# M624A.net
KiCad netlist of a schematic drawn in EAGLE
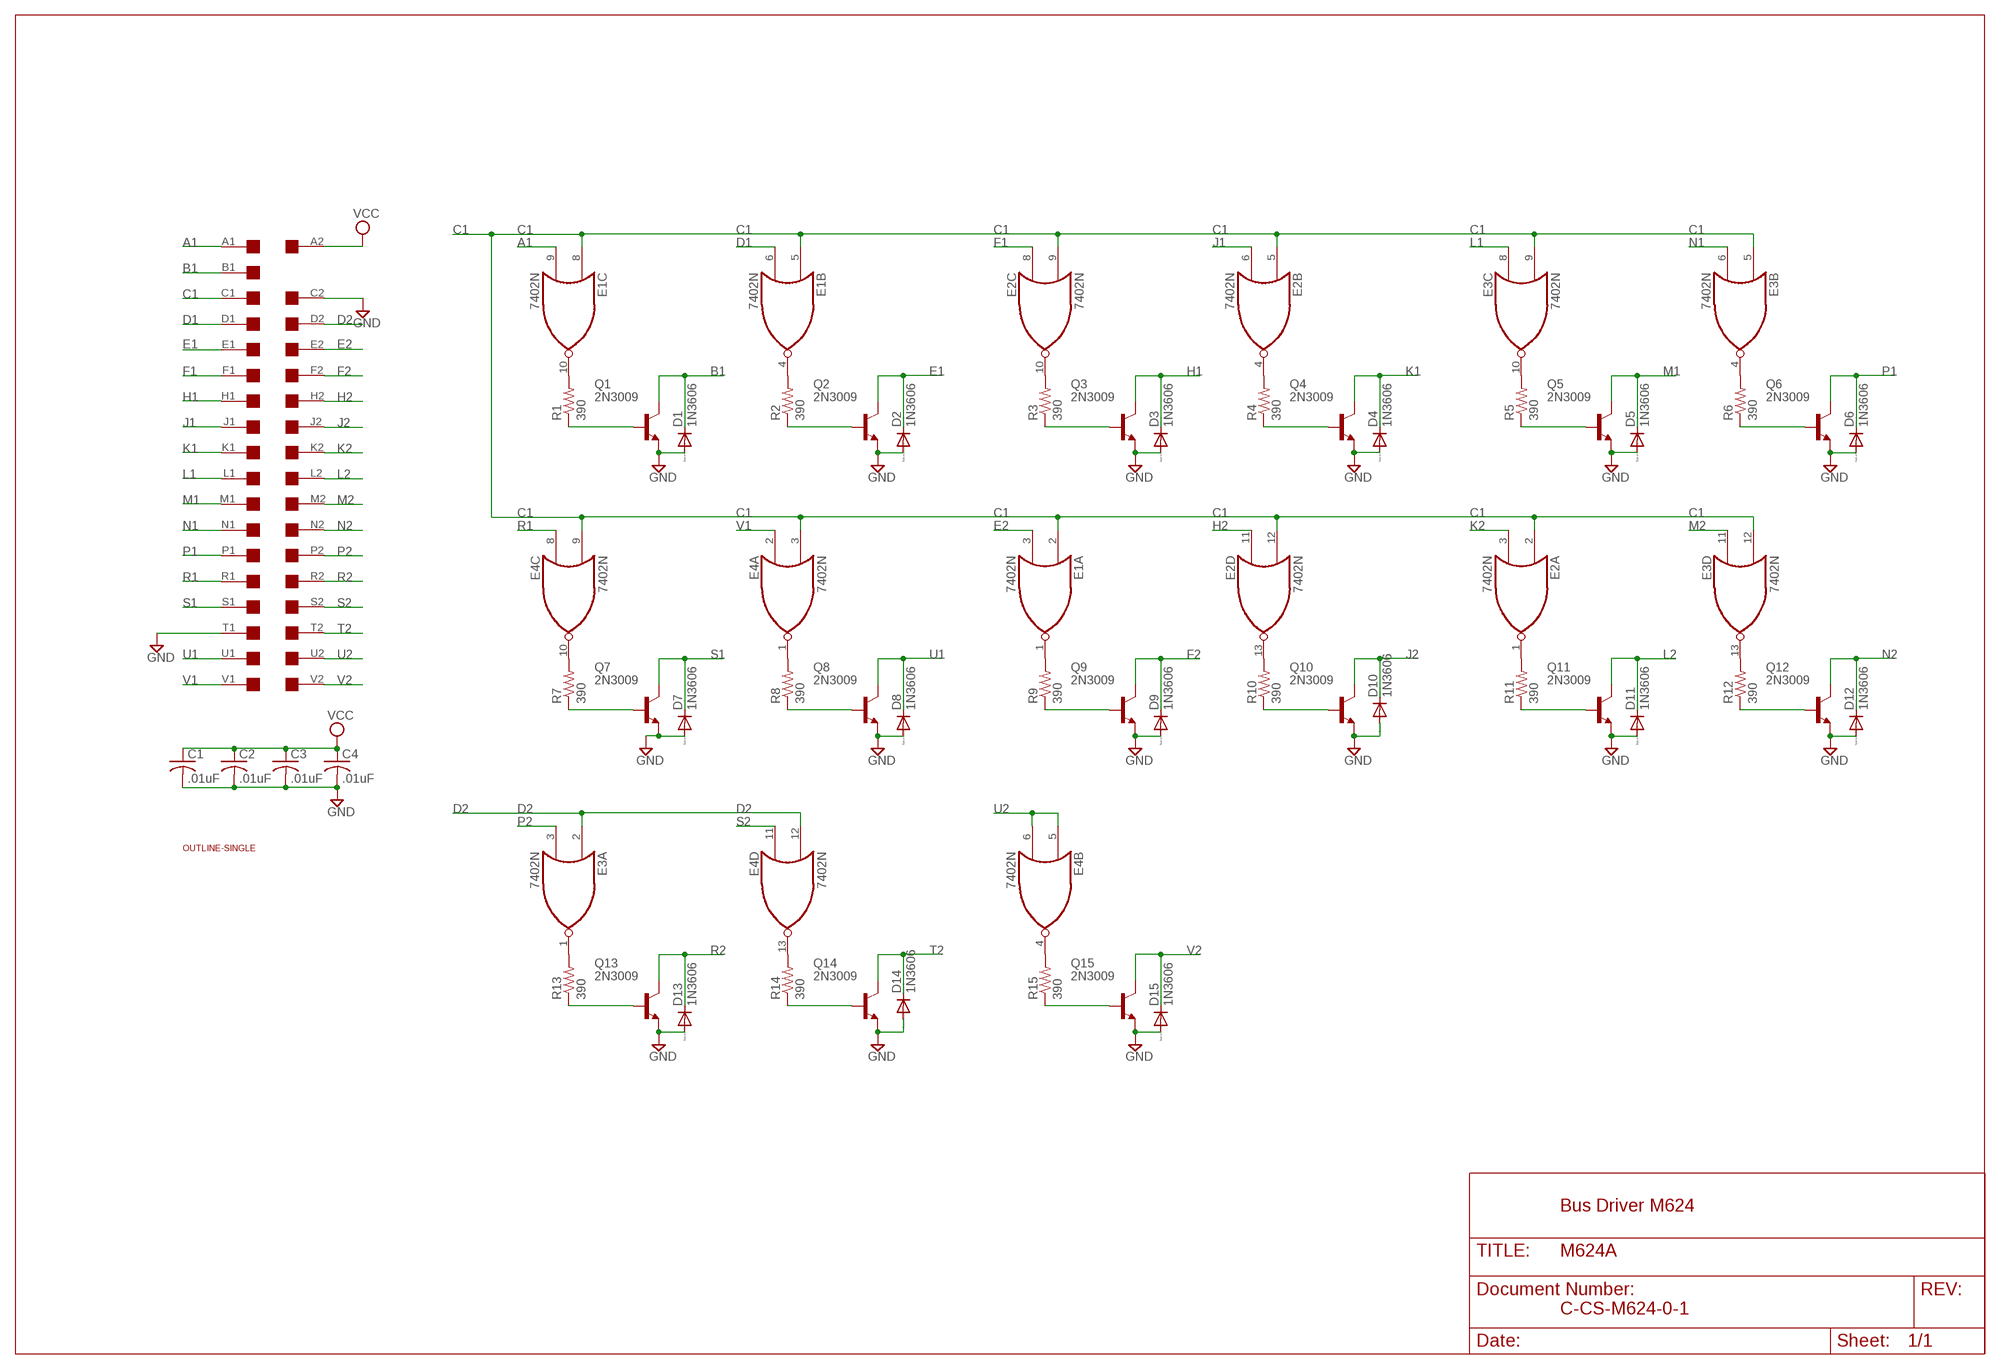
[diagram p0: schematic, sheet 1]

(export (version "E")
  (design (tool "Eeschema 10.0.6"))
  (components
    (comp (ref "C1")
      (value ".01uF")
      (footprint "eagle-import:C050-025X075")
      (libsource (lib "eagle-import") (part "C-US050-025X075"))
    )
    (comp (ref "C2")
      (value ".01uF")
      (footprint "eagle-import:C050-025X075")
      (libsource (lib "eagle-import") (part "C-US050-025X075"))
    )
    (comp (ref "C3")
      (value ".01uF")
      (footprint "eagle-import:C050-025X075")
      (libsource (lib "eagle-import") (part "C-US050-025X075"))
    )
    (comp (ref "C4")
      (value ".01uF")
      (footprint "eagle-import:C050-025X075")
      (libsource (lib "eagle-import") (part "C-US050-025X075"))
    )
    (comp (ref "D1")
      (value "1N3606")
      (footprint "eagle-import:DO35-10")
      (libsource (lib "eagle-import") (part "1N4148DO35-10"))
    )
    (comp (ref "D2")
      (value "1N3606")
      (footprint "eagle-import:DO35-10")
      (libsource (lib "eagle-import") (part "1N4148DO35-10"))
    )
    (comp (ref "D3")
      (value "1N3606")
      (footprint "eagle-import:DO35-10")
      (libsource (lib "eagle-import") (part "1N4148DO35-10"))
    )
    (comp (ref "D4")
      (value "1N3606")
      (footprint "eagle-import:DO35-10")
      (libsource (lib "eagle-import") (part "1N4148DO35-10"))
    )
    (comp (ref "D5")
      (value "1N3606")
      (footprint "eagle-import:DO35-10")
      (libsource (lib "eagle-import") (part "1N4148DO35-10"))
    )
    (comp (ref "D6")
      (value "1N3606")
      (footprint "eagle-import:DO35-10")
      (libsource (lib "eagle-import") (part "1N4148DO35-10"))
    )
    (comp (ref "D7")
      (value "1N3606")
      (footprint "eagle-import:DO35-10")
      (libsource (lib "eagle-import") (part "1N4148DO35-10"))
    )
    (comp (ref "D8")
      (value "1N3606")
      (footprint "eagle-import:DO35-10")
      (libsource (lib "eagle-import") (part "1N4148DO35-10"))
    )
    (comp (ref "D9")
      (value "1N3606")
      (footprint "eagle-import:DO35-10")
      (libsource (lib "eagle-import") (part "1N4148DO35-10"))
    )
    (comp (ref "D10")
      (value "1N3606")
      (footprint "eagle-import:DO35-10")
      (libsource (lib "eagle-import") (part "1N4148DO35-10"))
    )
    (comp (ref "D11")
      (value "1N3606")
      (footprint "eagle-import:DO35-10")
      (libsource (lib "eagle-import") (part "1N4148DO35-10"))
    )
    (comp (ref "D12")
      (value "1N3606")
      (footprint "eagle-import:DO35-10")
      (libsource (lib "eagle-import") (part "1N4148DO35-10"))
    )
    (comp (ref "D13")
      (value "1N3606")
      (footprint "eagle-import:DO35-10")
      (libsource (lib "eagle-import") (part "1N4148DO35-10"))
    )
    (comp (ref "D14")
      (value "1N3606")
      (footprint "eagle-import:DO35-10")
      (libsource (lib "eagle-import") (part "1N4148DO35-10"))
    )
    (comp (ref "D15")
      (value "1N3606")
      (footprint "eagle-import:DO35-10")
      (libsource (lib "eagle-import") (part "1N4148DO35-10"))
    )
    (comp (ref "E1")
      (value "7402N")
      (footprint "eagle-import:DIL14")
      (libsource (lib "eagle-import") (part "7402N"))
    )
    (comp (ref "E2")
      (value "7402N")
      (footprint "eagle-import:DIL14")
      (libsource (lib "eagle-import") (part "7402N"))
    )
    (comp (ref "E3")
      (value "7402N")
      (footprint "eagle-import:DIL14")
      (libsource (lib "eagle-import") (part "7402N"))
    )
    (comp (ref "E4")
      (value "7402N")
      (footprint "eagle-import:DIL14")
      (libsource (lib "eagle-import") (part "7402N"))
    )
    (comp (ref "Q1")
      (value "2N3009")
      (footprint "eagle-import:TO39")
      (libsource (lib "eagle-import") (part "-NPN-TO39-EBC2N1613"))
    )
    (comp (ref "Q2")
      (value "2N3009")
      (footprint "eagle-import:TO39")
      (libsource (lib "eagle-import") (part "-NPN-TO39-EBC2N1613"))
    )
    (comp (ref "Q3")
      (value "2N3009")
      (footprint "eagle-import:TO39")
      (libsource (lib "eagle-import") (part "-NPN-TO39-EBC2N1613"))
    )
    (comp (ref "Q4")
      (value "2N3009")
      (footprint "eagle-import:TO39")
      (libsource (lib "eagle-import") (part "-NPN-TO39-EBC2N1613"))
    )
    (comp (ref "Q5")
      (value "2N3009")
      (footprint "eagle-import:TO39")
      (libsource (lib "eagle-import") (part "-NPN-TO39-EBC2N1613"))
    )
    (comp (ref "Q6")
      (value "2N3009")
      (footprint "eagle-import:TO39")
      (libsource (lib "eagle-import") (part "-NPN-TO39-EBC2N1613"))
    )
    (comp (ref "Q7")
      (value "2N3009")
      (footprint "eagle-import:TO39")
      (libsource (lib "eagle-import") (part "-NPN-TO39-EBC2N1613"))
    )
    (comp (ref "Q8")
      (value "2N3009")
      (footprint "eagle-import:TO39")
      (libsource (lib "eagle-import") (part "-NPN-TO39-EBC2N1613"))
    )
    (comp (ref "Q9")
      (value "2N3009")
      (footprint "eagle-import:TO39")
      (libsource (lib "eagle-import") (part "-NPN-TO39-EBC2N1613"))
    )
    (comp (ref "Q10")
      (value "2N3009")
      (footprint "eagle-import:TO39")
      (libsource (lib "eagle-import") (part "-NPN-TO39-EBC2N1613"))
    )
    (comp (ref "Q11")
      (value "2N3009")
      (footprint "eagle-import:TO39")
      (libsource (lib "eagle-import") (part "-NPN-TO39-EBC2N1613"))
    )
    (comp (ref "Q12")
      (value "2N3009")
      (footprint "eagle-import:TO39")
      (libsource (lib "eagle-import") (part "-NPN-TO39-EBC2N1613"))
    )
    (comp (ref "Q13")
      (value "2N3009")
      (footprint "eagle-import:TO39")
      (libsource (lib "eagle-import") (part "-NPN-TO39-EBC2N1613"))
    )
    (comp (ref "Q14")
      (value "2N3009")
      (footprint "eagle-import:TO39")
      (libsource (lib "eagle-import") (part "-NPN-TO39-EBC2N1613"))
    )
    (comp (ref "Q15")
      (value "2N3009")
      (footprint "eagle-import:TO39")
      (libsource (lib "eagle-import") (part "-NPN-TO39-EBC2N1613"))
    )
    (comp (ref "R1")
      (value "390")
      (footprint "eagle-import:0207_10")
      (libsource (lib "eagle-import") (part "R-US_0207/10"))
    )
    (comp (ref "R2")
      (value "390")
      (footprint "eagle-import:0207_10")
      (libsource (lib "eagle-import") (part "R-US_0207/10"))
    )
    (comp (ref "R3")
      (value "390")
      (footprint "eagle-import:0207_10")
      (libsource (lib "eagle-import") (part "R-US_0207/10"))
    )
    (comp (ref "R4")
      (value "390")
      (footprint "eagle-import:0207_10")
      (libsource (lib "eagle-import") (part "R-US_0207/10"))
    )
    (comp (ref "R5")
      (value "390")
      (footprint "eagle-import:0207_10")
      (libsource (lib "eagle-import") (part "R-US_0207/10"))
    )
    (comp (ref "R6")
      (value "390")
      (footprint "eagle-import:0207_10")
      (libsource (lib "eagle-import") (part "R-US_0207/10"))
    )
    (comp (ref "R7")
      (value "390")
      (footprint "eagle-import:0207_10")
      (libsource (lib "eagle-import") (part "R-US_0207/10"))
    )
    (comp (ref "R8")
      (value "390")
      (footprint "eagle-import:0207_10")
      (libsource (lib "eagle-import") (part "R-US_0207/10"))
    )
    (comp (ref "R9")
      (value "390")
      (footprint "eagle-import:0207_10")
      (libsource (lib "eagle-import") (part "R-US_0207/10"))
    )
    (comp (ref "R10")
      (value "390")
      (footprint "eagle-import:0207_10")
      (libsource (lib "eagle-import") (part "R-US_0207/10"))
    )
    (comp (ref "R11")
      (value "390")
      (footprint "eagle-import:0207_10")
      (libsource (lib "eagle-import") (part "R-US_0207/10"))
    )
    (comp (ref "R12")
      (value "390")
      (footprint "eagle-import:0207_10")
      (libsource (lib "eagle-import") (part "R-US_0207/10"))
    )
    (comp (ref "R13")
      (value "390")
      (footprint "eagle-import:0207_10")
      (libsource (lib "eagle-import") (part "R-US_0207/10"))
    )
    (comp (ref "R14")
      (value "390")
      (footprint "eagle-import:0207_10")
      (libsource (lib "eagle-import") (part "R-US_0207/10"))
    )
    (comp (ref "R15")
      (value "390")
      (footprint "eagle-import:0207_10")
      (libsource (lib "eagle-import") (part "R-US_0207/10"))
    )
    (comp (ref "U$1")
      (value "OUTLINE-SINGLE")
      (footprint "eagle-import:SINGLE")
      (libsource (lib "eagle-import") (part "OUTLINE-SINGLE"))
    )
    (comp (ref "U$4")
      (value "SINGLE")
      (footprint "eagle-import:EDGE-CON2")
      (libsource (lib "eagle-import") (part "SINGLE"))
    )
  )
  (nets
    (net (code "1") (name "/A1") (class "Default")
      (node (ref "E1") (pin "9") (pinfunction "I1_9") (pintype "input"))
      (node (ref "U$4") (pin "A1") (pinfunction "1_A1") (pintype "bidirectional"))
    )
    (net (code "2") (name "/B1") (class "Default")
      (node (ref "D1") (pin "C") (pinfunction "C_C") (pintype "passive"))
      (node (ref "Q1") (pin "3") (pinfunction "C_3") (pintype "passive"))
      (node (ref "U$4") (pin "B1") (pinfunction "1_B1") (pintype "bidirectional"))
    )
    (net (code "3") (name "/C1") (class "Default")
      (node (ref "E1") (pin "2") (pinfunction "I0_2") (pintype "input"))
      (node (ref "E1") (pin "5") (pinfunction "I0_5") (pintype "input"))
      (node (ref "E1") (pin "8") (pinfunction "I0_8") (pintype "input"))
      (node (ref "E2") (pin "12") (pinfunction "I1_12") (pintype "input"))
      (node (ref "E2") (pin "2") (pinfunction "I0_2") (pintype "input"))
      (node (ref "E2") (pin "5") (pinfunction "I0_5") (pintype "input"))
      (node (ref "E2") (pin "9") (pinfunction "I1_9") (pintype "input"))
      (node (ref "E3") (pin "12") (pinfunction "I1_12") (pintype "input"))
      (node (ref "E3") (pin "5") (pinfunction "I0_5") (pintype "input"))
      (node (ref "E3") (pin "9") (pinfunction "I1_9") (pintype "input"))
      (node (ref "E4") (pin "3") (pinfunction "I1_3") (pintype "input"))
      (node (ref "E4") (pin "9") (pinfunction "I1_9") (pintype "input"))
      (node (ref "U$4") (pin "C1") (pinfunction "1_C1") (pintype "bidirectional"))
    )
    (net (code "4") (name "/D1") (class "Default")
      (node (ref "E1") (pin "6") (pinfunction "I1_6") (pintype "input"))
      (node (ref "U$4") (pin "D1") (pinfunction "1_D1") (pintype "bidirectional"))
    )
    (net (code "5") (name "/D2") (class "Default")
      (node (ref "E3") (pin "2") (pinfunction "I0_2") (pintype "input"))
      (node (ref "E4") (pin "12") (pinfunction "I1_12") (pintype "input"))
      (node (ref "U$4") (pin "D2") (pinfunction "1_D2") (pintype "bidirectional"))
    )
    (net (code "6") (name "/E1") (class "Default")
      (node (ref "D2") (pin "C") (pinfunction "C_C") (pintype "passive"))
      (node (ref "Q2") (pin "3") (pinfunction "C_3") (pintype "passive"))
      (node (ref "U$4") (pin "E1") (pinfunction "1_E1") (pintype "bidirectional"))
    )
    (net (code "7") (name "/E2") (class "Default")
      (node (ref "E1") (pin "3") (pinfunction "I1_3") (pintype "input"))
      (node (ref "U$4") (pin "E2") (pinfunction "1_E2") (pintype "bidirectional"))
    )
    (net (code "8") (name "/F1") (class "Default")
      (node (ref "E2") (pin "8") (pinfunction "I0_8") (pintype "input"))
      (node (ref "U$4") (pin "F1") (pinfunction "1_F1") (pintype "bidirectional"))
    )
    (net (code "9") (name "/F2") (class "Default")
      (node (ref "D9") (pin "C") (pinfunction "C_C") (pintype "passive"))
      (node (ref "Q9") (pin "3") (pinfunction "C_3") (pintype "passive"))
      (node (ref "U$4") (pin "F2") (pinfunction "1_F2") (pintype "bidirectional"))
    )
    (net (code "10") (name "/H1") (class "Default")
      (node (ref "D3") (pin "C") (pinfunction "C_C") (pintype "passive"))
      (node (ref "Q3") (pin "3") (pinfunction "C_3") (pintype "passive"))
      (node (ref "U$4") (pin "H1") (pinfunction "1_H1") (pintype "bidirectional"))
    )
    (net (code "11") (name "/H2") (class "Default")
      (node (ref "E2") (pin "11") (pinfunction "I0_11") (pintype "input"))
      (node (ref "U$4") (pin "H2") (pinfunction "1_H2") (pintype "bidirectional"))
    )
    (net (code "12") (name "/J1") (class "Default")
      (node (ref "E2") (pin "6") (pinfunction "I1_6") (pintype "input"))
      (node (ref "U$4") (pin "J1") (pinfunction "1_J1") (pintype "bidirectional"))
    )
    (net (code "13") (name "/J2") (class "Default")
      (node (ref "D10") (pin "C") (pinfunction "C_C") (pintype "passive"))
      (node (ref "Q10") (pin "3") (pinfunction "C_3") (pintype "passive"))
      (node (ref "U$4") (pin "J2") (pinfunction "1_J2") (pintype "bidirectional"))
    )
    (net (code "14") (name "/K1") (class "Default")
      (node (ref "D4") (pin "C") (pinfunction "C_C") (pintype "passive"))
      (node (ref "Q4") (pin "3") (pinfunction "C_3") (pintype "passive"))
      (node (ref "U$4") (pin "K1") (pinfunction "1_K1") (pintype "bidirectional"))
    )
    (net (code "15") (name "/K2") (class "Default")
      (node (ref "E2") (pin "3") (pinfunction "I1_3") (pintype "input"))
      (node (ref "U$4") (pin "K2") (pinfunction "1_K2") (pintype "bidirectional"))
    )
    (net (code "16") (name "/L1") (class "Default")
      (node (ref "E3") (pin "8") (pinfunction "I0_8") (pintype "input"))
      (node (ref "U$4") (pin "L1") (pinfunction "1_L1") (pintype "bidirectional"))
    )
    (net (code "17") (name "/L2") (class "Default")
      (node (ref "D11") (pin "C") (pinfunction "C_C") (pintype "passive"))
      (node (ref "Q11") (pin "3") (pinfunction "C_3") (pintype "passive"))
      (node (ref "U$4") (pin "L2") (pinfunction "1_L2") (pintype "bidirectional"))
    )
    (net (code "18") (name "/M1") (class "Default")
      (node (ref "D5") (pin "C") (pinfunction "C_C") (pintype "passive"))
      (node (ref "Q5") (pin "3") (pinfunction "C_3") (pintype "passive"))
      (node (ref "U$4") (pin "M1") (pinfunction "1_M1") (pintype "bidirectional"))
    )
    (net (code "19") (name "/M2") (class "Default")
      (node (ref "E3") (pin "11") (pinfunction "I0_11") (pintype "input"))
      (node (ref "U$4") (pin "M2") (pinfunction "1_M2") (pintype "bidirectional"))
    )
    (net (code "20") (name "/N1") (class "Default")
      (node (ref "E3") (pin "6") (pinfunction "I1_6") (pintype "input"))
      (node (ref "U$4") (pin "N1") (pinfunction "1_N1") (pintype "bidirectional"))
    )
    (net (code "21") (name "/N2") (class "Default")
      (node (ref "D12") (pin "C") (pinfunction "C_C") (pintype "passive"))
      (node (ref "Q12") (pin "3") (pinfunction "C_3") (pintype "passive"))
      (node (ref "U$4") (pin "N2") (pinfunction "1_N2") (pintype "bidirectional"))
    )
    (net (code "22") (name "/P1") (class "Default")
      (node (ref "D6") (pin "C") (pinfunction "C_C") (pintype "passive"))
      (node (ref "Q6") (pin "3") (pinfunction "C_3") (pintype "passive"))
      (node (ref "U$4") (pin "P1") (pinfunction "1_P1") (pintype "bidirectional"))
    )
    (net (code "23") (name "/P2") (class "Default")
      (node (ref "E3") (pin "3") (pinfunction "I1_3") (pintype "input"))
      (node (ref "U$4") (pin "P2") (pinfunction "1_P2") (pintype "bidirectional"))
    )
    (net (code "24") (name "/R1") (class "Default")
      (node (ref "E4") (pin "8") (pinfunction "I0_8") (pintype "input"))
      (node (ref "U$4") (pin "R1") (pinfunction "1_R1") (pintype "bidirectional"))
    )
    (net (code "25") (name "/R2") (class "Default")
      (node (ref "D13") (pin "C") (pinfunction "C_C") (pintype "passive"))
      (node (ref "Q13") (pin "3") (pinfunction "C_3") (pintype "passive"))
      (node (ref "U$4") (pin "R2") (pinfunction "1_R2") (pintype "bidirectional"))
    )
    (net (code "26") (name "/S1") (class "Default")
      (node (ref "D7") (pin "C") (pinfunction "C_C") (pintype "passive"))
      (node (ref "Q7") (pin "3") (pinfunction "C_3") (pintype "passive"))
      (node (ref "U$4") (pin "S1") (pinfunction "1_S1") (pintype "bidirectional"))
    )
    (net (code "27") (name "/S2") (class "Default")
      (node (ref "E4") (pin "11") (pinfunction "I0_11") (pintype "input"))
      (node (ref "U$4") (pin "S2") (pinfunction "1_S2") (pintype "bidirectional"))
    )
    (net (code "28") (name "/T2") (class "Default")
      (node (ref "D14") (pin "C") (pinfunction "C_C") (pintype "passive"))
      (node (ref "Q14") (pin "3") (pinfunction "C_3") (pintype "passive"))
      (node (ref "U$4") (pin "T2") (pinfunction "1_T2") (pintype "bidirectional"))
    )
    (net (code "29") (name "/U1") (class "Default")
      (node (ref "D8") (pin "C") (pinfunction "C_C") (pintype "passive"))
      (node (ref "Q8") (pin "3") (pinfunction "C_3") (pintype "passive"))
      (node (ref "U$4") (pin "U1") (pinfunction "1_U1") (pintype "bidirectional"))
    )
    (net (code "30") (name "/U2") (class "Default")
      (node (ref "E4") (pin "5") (pinfunction "I0_5") (pintype "input"))
      (node (ref "E4") (pin "6") (pinfunction "I1_6") (pintype "input"))
      (node (ref "U$4") (pin "U2") (pinfunction "1_U2") (pintype "bidirectional"))
    )
    (net (code "31") (name "/V1") (class "Default")
      (node (ref "E4") (pin "2") (pinfunction "I0_2") (pintype "input"))
      (node (ref "U$4") (pin "V1") (pinfunction "1_V1") (pintype "bidirectional"))
    )
    (net (code "32") (name "/V2") (class "Default")
      (node (ref "D15") (pin "C") (pinfunction "C_C") (pintype "passive"))
      (node (ref "Q15") (pin "3") (pinfunction "C_3") (pintype "passive"))
      (node (ref "U$4") (pin "V2") (pinfunction "1_V2") (pintype "bidirectional"))
    )
    (net (code "33") (name "GND") (class "Default")
      (node (ref "C1") (pin "2") (pinfunction "2_2") (pintype "passive"))
      (node (ref "C2") (pin "2") (pinfunction "2_2") (pintype "passive"))
      (node (ref "C3") (pin "2") (pinfunction "2_2") (pintype "passive"))
      (node (ref "C4") (pin "2") (pinfunction "2_2") (pintype "passive"))
      (node (ref "D1") (pin "A") (pinfunction "A_A") (pintype "passive"))
      (node (ref "D10") (pin "A") (pinfunction "A_A") (pintype "passive"))
      (node (ref "D11") (pin "A") (pinfunction "A_A") (pintype "passive"))
      (node (ref "D12") (pin "A") (pinfunction "A_A") (pintype "passive"))
      (node (ref "D13") (pin "A") (pinfunction "A_A") (pintype "passive"))
      (node (ref "D14") (pin "A") (pinfunction "A_A") (pintype "passive"))
      (node (ref "D15") (pin "A") (pinfunction "A_A") (pintype "passive"))
      (node (ref "D2") (pin "A") (pinfunction "A_A") (pintype "passive"))
      (node (ref "D3") (pin "A") (pinfunction "A_A") (pintype "passive"))
      (node (ref "D4") (pin "A") (pinfunction "A_A") (pintype "passive"))
      (node (ref "D5") (pin "A") (pinfunction "A_A") (pintype "passive"))
      (node (ref "D6") (pin "A") (pinfunction "A_A") (pintype "passive"))
      (node (ref "D7") (pin "A") (pinfunction "A_A") (pintype "passive"))
      (node (ref "D8") (pin "A") (pinfunction "A_A") (pintype "passive"))
      (node (ref "D9") (pin "A") (pinfunction "A_A") (pintype "passive"))
      (node (ref "Q1") (pin "1") (pinfunction "E_1") (pintype "passive"))
      (node (ref "Q10") (pin "1") (pinfunction "E_1") (pintype "passive"))
      (node (ref "Q11") (pin "1") (pinfunction "E_1") (pintype "passive"))
      (node (ref "Q12") (pin "1") (pinfunction "E_1") (pintype "passive"))
      (node (ref "Q13") (pin "1") (pinfunction "E_1") (pintype "passive"))
      (node (ref "Q14") (pin "1") (pinfunction "E_1") (pintype "passive"))
      (node (ref "Q15") (pin "1") (pinfunction "E_1") (pintype "passive"))
      (node (ref "Q2") (pin "1") (pinfunction "E_1") (pintype "passive"))
      (node (ref "Q3") (pin "1") (pinfunction "E_1") (pintype "passive"))
      (node (ref "Q4") (pin "1") (pinfunction "E_1") (pintype "passive"))
      (node (ref "Q5") (pin "1") (pinfunction "E_1") (pintype "passive"))
      (node (ref "Q6") (pin "1") (pinfunction "E_1") (pintype "passive"))
      (node (ref "Q7") (pin "1") (pinfunction "E_1") (pintype "passive"))
      (node (ref "Q8") (pin "1") (pinfunction "E_1") (pintype "passive"))
      (node (ref "Q9") (pin "1") (pinfunction "E_1") (pintype "passive"))
      (node (ref "U$4") (pin "C2") (pinfunction "1_C2") (pintype "bidirectional"))
      (node (ref "U$4") (pin "T1") (pinfunction "1_T1") (pintype "bidirectional"))
    )
    (net (code "34") (name "Net-(E1A-O)") (class "Default")
      (node (ref "E1") (pin "1") (pinfunction "O_1") (pintype "output"))
      (node (ref "R9") (pin "2") (pinfunction "2_2") (pintype "passive"))
    )
    (net (code "35") (name "Net-(E1B-O)") (class "Default")
      (node (ref "E1") (pin "4") (pinfunction "O_4") (pintype "output"))
      (node (ref "R2") (pin "2") (pinfunction "2_2") (pintype "passive"))
    )
    (net (code "36") (name "Net-(E1C-O)") (class "Default")
      (node (ref "E1") (pin "10") (pinfunction "O_10") (pintype "output"))
      (node (ref "R1") (pin "2") (pinfunction "2_2") (pintype "passive"))
    )
    (net (code "37") (name "Net-(E2A-O)") (class "Default")
      (node (ref "E2") (pin "1") (pinfunction "O_1") (pintype "output"))
      (node (ref "R11") (pin "2") (pinfunction "2_2") (pintype "passive"))
    )
    (net (code "38") (name "Net-(E2B-O)") (class "Default")
      (node (ref "E2") (pin "4") (pinfunction "O_4") (pintype "output"))
      (node (ref "R4") (pin "2") (pinfunction "2_2") (pintype "passive"))
    )
    (net (code "39") (name "Net-(E2C-O)") (class "Default")
      (node (ref "E2") (pin "10") (pinfunction "O_10") (pintype "output"))
      (node (ref "R3") (pin "2") (pinfunction "2_2") (pintype "passive"))
    )
    (net (code "40") (name "Net-(E2D-O)") (class "Default")
      (node (ref "E2") (pin "13") (pinfunction "O_13") (pintype "output"))
      (node (ref "R10") (pin "2") (pinfunction "2_2") (pintype "passive"))
    )
    (net (code "41") (name "Net-(E3A-O)") (class "Default")
      (node (ref "E3") (pin "1") (pinfunction "O_1") (pintype "output"))
      (node (ref "R13") (pin "2") (pinfunction "2_2") (pintype "passive"))
    )
    (net (code "42") (name "Net-(E3B-O)") (class "Default")
      (node (ref "E3") (pin "4") (pinfunction "O_4") (pintype "output"))
      (node (ref "R6") (pin "2") (pinfunction "2_2") (pintype "passive"))
    )
    (net (code "43") (name "Net-(E3C-O)") (class "Default")
      (node (ref "E3") (pin "10") (pinfunction "O_10") (pintype "output"))
      (node (ref "R5") (pin "2") (pinfunction "2_2") (pintype "passive"))
    )
    (net (code "44") (name "Net-(E3D-O)") (class "Default")
      (node (ref "E3") (pin "13") (pinfunction "O_13") (pintype "output"))
      (node (ref "R12") (pin "2") (pinfunction "2_2") (pintype "passive"))
    )
    (net (code "45") (name "Net-(E4A-O)") (class "Default")
      (node (ref "E4") (pin "1") (pinfunction "O_1") (pintype "output"))
      (node (ref "R8") (pin "2") (pinfunction "2_2") (pintype "passive"))
    )
    (net (code "46") (name "Net-(E4B-O)") (class "Default")
      (node (ref "E4") (pin "4") (pinfunction "O_4") (pintype "output"))
      (node (ref "R15") (pin "2") (pinfunction "2_2") (pintype "passive"))
    )
    (net (code "47") (name "Net-(E4C-O)") (class "Default")
      (node (ref "E4") (pin "10") (pinfunction "O_10") (pintype "output"))
      (node (ref "R7") (pin "2") (pinfunction "2_2") (pintype "passive"))
    )
    (net (code "48") (name "Net-(E4D-O)") (class "Default")
      (node (ref "E4") (pin "13") (pinfunction "O_13") (pintype "output"))
      (node (ref "R14") (pin "2") (pinfunction "2_2") (pintype "passive"))
    )
    (net (code "49") (name "Net-(Q1-B)") (class "Default")
      (node (ref "Q1") (pin "2") (pinfunction "B_2") (pintype "passive"))
      (node (ref "R1") (pin "1") (pinfunction "1_1") (pintype "passive"))
    )
    (net (code "50") (name "Net-(Q2-B)") (class "Default")
      (node (ref "Q2") (pin "2") (pinfunction "B_2") (pintype "passive"))
      (node (ref "R2") (pin "1") (pinfunction "1_1") (pintype "passive"))
    )
    (net (code "51") (name "Net-(Q3-B)") (class "Default")
      (node (ref "Q3") (pin "2") (pinfunction "B_2") (pintype "passive"))
      (node (ref "R3") (pin "1") (pinfunction "1_1") (pintype "passive"))
    )
    (net (code "52") (name "Net-(Q4-B)") (class "Default")
      (node (ref "Q4") (pin "2") (pinfunction "B_2") (pintype "passive"))
      (node (ref "R4") (pin "1") (pinfunction "1_1") (pintype "passive"))
    )
    (net (code "53") (name "Net-(Q5-B)") (class "Default")
      (node (ref "Q5") (pin "2") (pinfunction "B_2") (pintype "passive"))
      (node (ref "R5") (pin "1") (pinfunction "1_1") (pintype "passive"))
    )
    (net (code "54") (name "Net-(Q6-B)") (class "Default")
      (node (ref "Q6") (pin "2") (pinfunction "B_2") (pintype "passive"))
      (node (ref "R6") (pin "1") (pinfunction "1_1") (pintype "passive"))
    )
    (net (code "55") (name "Net-(Q7-B)") (class "Default")
      (node (ref "Q7") (pin "2") (pinfunction "B_2") (pintype "passive"))
      (node (ref "R7") (pin "1") (pinfunction "1_1") (pintype "passive"))
    )
    (net (code "56") (name "Net-(Q8-B)") (class "Default")
      (node (ref "Q8") (pin "2") (pinfunction "B_2") (pintype "passive"))
      (node (ref "R8") (pin "1") (pinfunction "1_1") (pintype "passive"))
    )
    (net (code "57") (name "Net-(Q9-B)") (class "Default")
      (node (ref "Q9") (pin "2") (pinfunction "B_2") (pintype "passive"))
      (node (ref "R9") (pin "1") (pinfunction "1_1") (pintype "passive"))
    )
    (net (code "58") (name "Net-(Q10-B)") (class "Default")
      (node (ref "Q10") (pin "2") (pinfunction "B_2") (pintype "passive"))
      (node (ref "R10") (pin "1") (pinfunction "1_1") (pintype "passive"))
    )
    (net (code "59") (name "Net-(Q11-B)") (class "Default")
      (node (ref "Q11") (pin "2") (pinfunction "B_2") (pintype "passive"))
      (node (ref "R11") (pin "1") (pinfunction "1_1") (pintype "passive"))
    )
    (net (code "60") (name "Net-(Q12-B)") (class "Default")
      (node (ref "Q12") (pin "2") (pinfunction "B_2") (pintype "passive"))
      (node (ref "R12") (pin "1") (pinfunction "1_1") (pintype "passive"))
    )
    (net (code "61") (name "Net-(Q13-B)") (class "Default")
      (node (ref "Q13") (pin "2") (pinfunction "B_2") (pintype "passive"))
      (node (ref "R13") (pin "1") (pinfunction "1_1") (pintype "passive"))
    )
    (net (code "62") (name "Net-(Q14-B)") (class "Default")
      (node (ref "Q14") (pin "2") (pinfunction "B_2") (pintype "passive"))
      (node (ref "R14") (pin "1") (pinfunction "1_1") (pintype "passive"))
    )
    (net (code "63") (name "Net-(Q15-B)") (class "Default")
      (node (ref "Q15") (pin "2") (pinfunction "B_2") (pintype "passive"))
      (node (ref "R15") (pin "1") (pinfunction "1_1") (pintype "passive"))
    )
    (net (code "64") (name "VCC") (class "Default")
      (node (ref "C1") (pin "1") (pinfunction "1_1") (pintype "passive"))
      (node (ref "C2") (pin "1") (pinfunction "1_1") (pintype "passive"))
      (node (ref "C3") (pin "1") (pinfunction "1_1") (pintype "passive"))
      (node (ref "C4") (pin "1") (pinfunction "1_1") (pintype "passive"))
      (node (ref "U$4") (pin "A2") (pinfunction "1_A2") (pintype "bidirectional"))
    )
  )
)
